# Schema_IOExp_De_Windt_Kyell.net
KiCad netlist of a schematic drawn in EAGLE
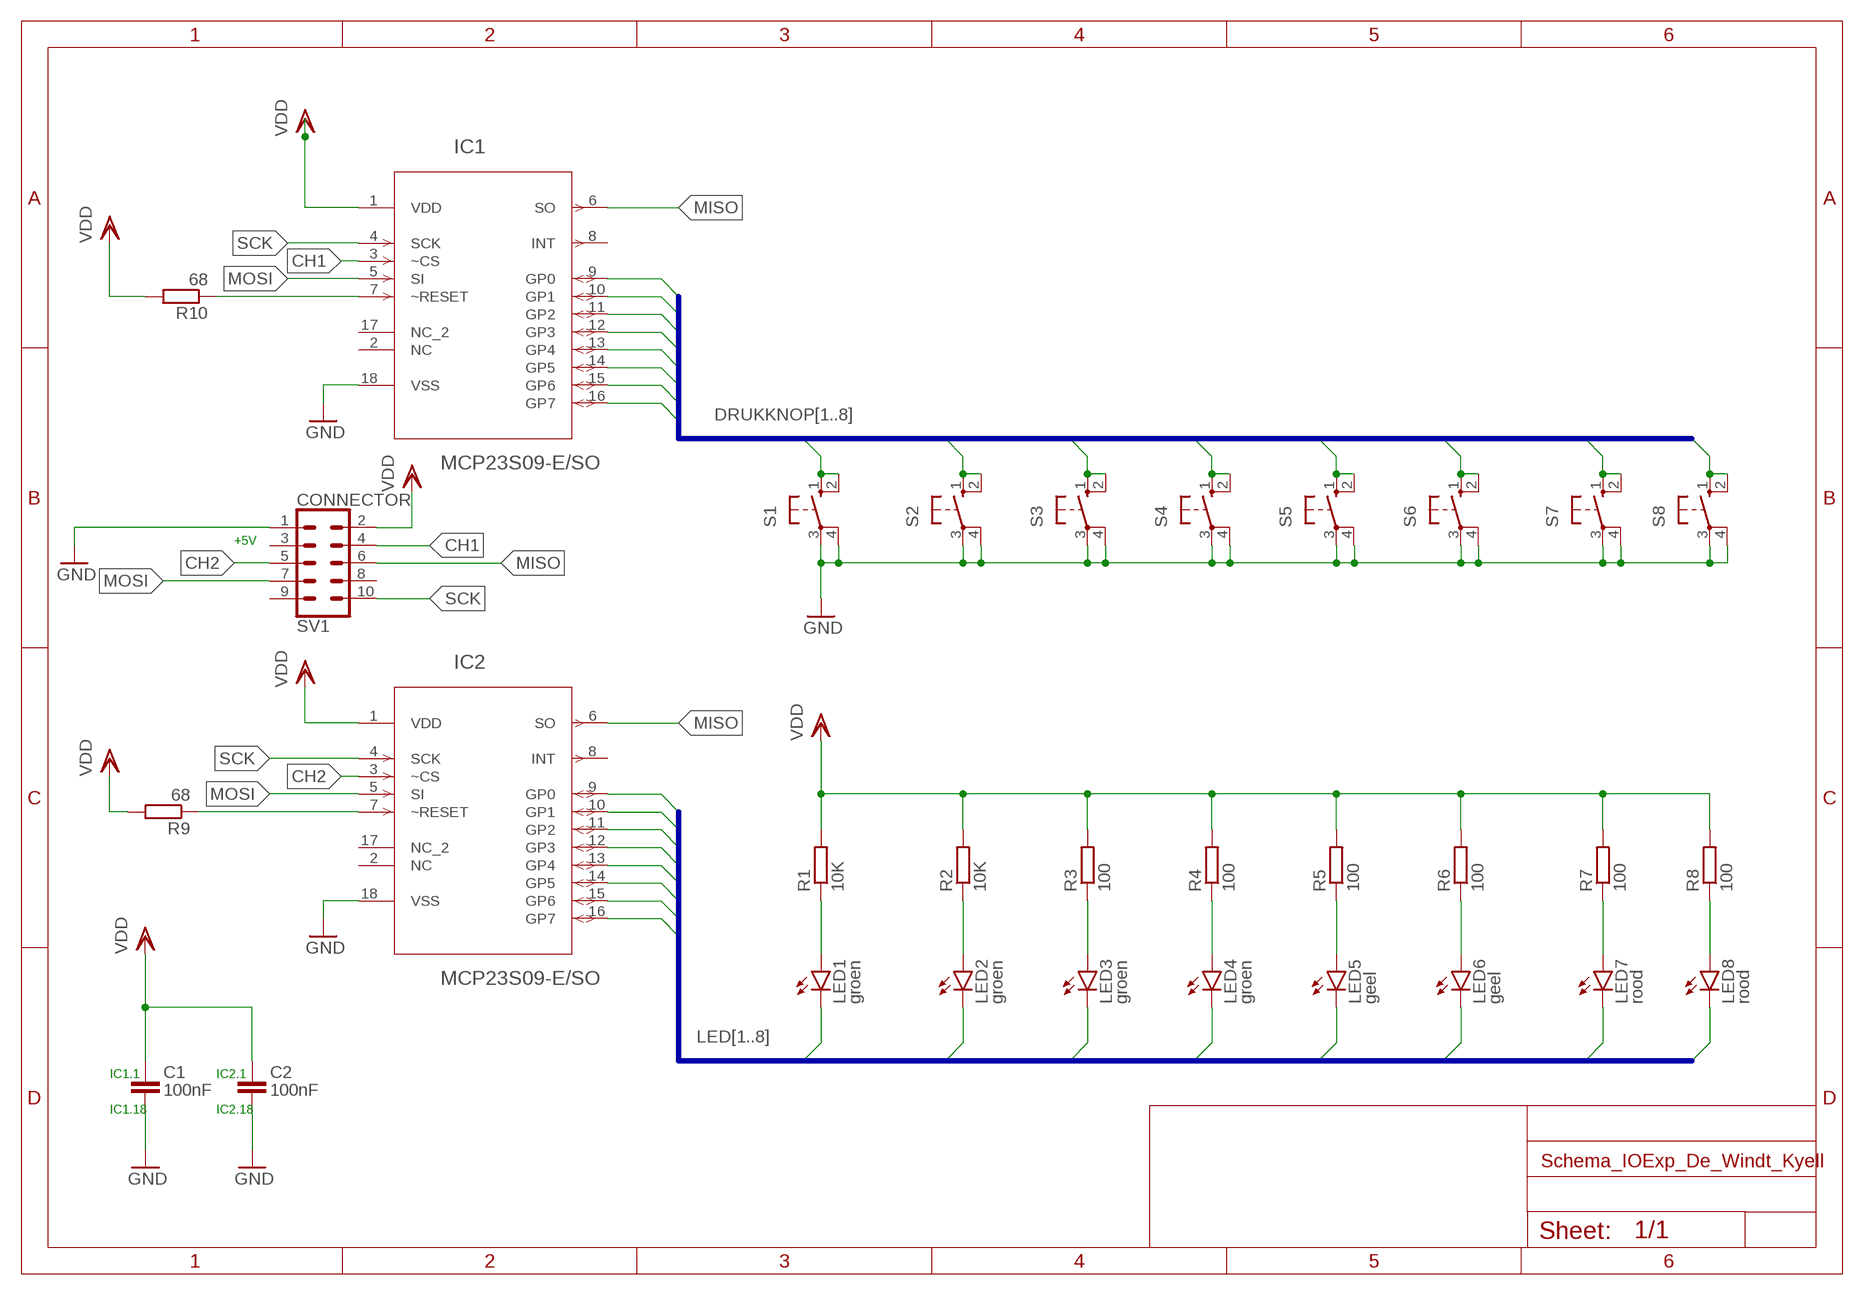
[diagram p0: schematic, sheet 1]

(export (version "E")
  (design (tool "Eeschema 10.0.6"))
  (components
    (comp (ref "C1")
      (value "100nF")
      (footprint "eagle-import:C0805K")
      (libsource (lib "eagle-import") (part "CAPACITORC0805K"))
    )
    (comp (ref "C2")
      (value "100nF")
      (footprint "eagle-import:C0805K")
      (libsource (lib "eagle-import") (part "CAPACITORC0805K"))
    )
    (comp (ref "CONNECTOR")
      (value "SV1")
      (footprint "eagle-import:2X5-SHROUDED")
      (libsource (lib "eagle-import") (part "CONN_05X2SHD"))
    )
    (comp (ref "IC1")
      (value "MCP23S09-E/SO")
      (footprint "eagle-import:SOIC127P1030X265-18N")
      (fields (field (name "MPN") "McP23S09-E/SO"))
      (libsource (lib "eagle-import") (part "MCP23S09-E/SO"))
    )
    (comp (ref "IC2")
      (value "MCP23S09-E/SO")
      (footprint "eagle-import:SOIC127P1030X265-18N")
      (fields (field (name "MPN") "McP23S09-E/SO"))
      (libsource (lib "eagle-import") (part "MCP23S09-E/SO"))
    )
    (comp (ref "LED1")
      (value "groen")
      (footprint "eagle-import:CHIPLED_0805")
      (libsource (lib "eagle-import") (part "LEDCHIPLED_0805"))
    )
    (comp (ref "LED2")
      (value "groen")
      (footprint "eagle-import:CHIPLED_0805")
      (libsource (lib "eagle-import") (part "LEDCHIPLED_0805"))
    )
    (comp (ref "LED3")
      (value "groen")
      (footprint "eagle-import:CHIPLED_0805")
      (libsource (lib "eagle-import") (part "LEDCHIPLED_0805"))
    )
    (comp (ref "LED4")
      (value "groen")
      (footprint "eagle-import:CHIPLED_0805")
      (libsource (lib "eagle-import") (part "LEDCHIPLED_0805"))
    )
    (comp (ref "LED5")
      (value "geel")
      (footprint "eagle-import:CHIPLED_0805")
      (libsource (lib "eagle-import") (part "LEDCHIPLED_0805"))
    )
    (comp (ref "LED6")
      (value "geel")
      (footprint "eagle-import:CHIPLED_0805")
      (libsource (lib "eagle-import") (part "LEDCHIPLED_0805"))
    )
    (comp (ref "LED7")
      (value "rood")
      (footprint "eagle-import:CHIPLED_0805")
      (libsource (lib "eagle-import") (part "LEDCHIPLED_0805"))
    )
    (comp (ref "LED8")
      (value "rood")
      (footprint "eagle-import:CHIPLED_0805")
      (libsource (lib "eagle-import") (part "LEDCHIPLED_0805"))
    )
    (comp (ref "R1")
      (value "10K")
      (footprint "eagle-import:R0805")
      (libsource (lib "eagle-import") (part "R-EU_R0805"))
    )
    (comp (ref "R2")
      (value "10K")
      (footprint "eagle-import:R0805")
      (libsource (lib "eagle-import") (part "R-EU_R0805"))
    )
    (comp (ref "R3")
      (value "100")
      (footprint "eagle-import:R0805")
      (libsource (lib "eagle-import") (part "R-EU_R0805"))
    )
    (comp (ref "R4")
      (value "100")
      (footprint "eagle-import:R0805")
      (libsource (lib "eagle-import") (part "R-EU_R0805"))
    )
    (comp (ref "R5")
      (value "100")
      (footprint "eagle-import:R0805")
      (libsource (lib "eagle-import") (part "R-EU_R0805"))
    )
    (comp (ref "R6")
      (value "100")
      (footprint "eagle-import:R0805")
      (libsource (lib "eagle-import") (part "R-EU_R0805"))
    )
    (comp (ref "R7")
      (value "100")
      (footprint "eagle-import:R0805")
      (libsource (lib "eagle-import") (part "R-EU_R0805"))
    )
    (comp (ref "R8")
      (value "100")
      (footprint "eagle-import:R0805")
      (libsource (lib "eagle-import") (part "R-EU_R0805"))
    )
    (comp (ref "R9")
      (value "68")
      (footprint "eagle-import:R0805")
      (libsource (lib "eagle-import") (part "R-EU_R0805"))
    )
    (comp (ref "R10")
      (value "68")
      (footprint "eagle-import:R0805")
      (libsource (lib "eagle-import") (part "R-EU_R0805"))
    )
    (comp (ref "S1")
      (value "10-XX")
      (footprint "eagle-import:B3F-10XX")
      (fields (field (name "MPN") "B3F-1000"))
      (libsource (lib "eagle-import") (part "10-XX"))
    )
    (comp (ref "S2")
      (value "10-XX")
      (footprint "eagle-import:B3F-10XX")
      (fields (field (name "MPN") "B3F-1000"))
      (libsource (lib "eagle-import") (part "10-XX"))
    )
    (comp (ref "S3")
      (value "10-XX")
      (footprint "eagle-import:B3F-10XX")
      (fields (field (name "MPN") "B3F-1000"))
      (libsource (lib "eagle-import") (part "10-XX"))
    )
    (comp (ref "S4")
      (value "10-XX")
      (footprint "eagle-import:B3F-10XX")
      (fields (field (name "MPN") "B3F-1000"))
      (libsource (lib "eagle-import") (part "10-XX"))
    )
    (comp (ref "S5")
      (value "10-XX")
      (footprint "eagle-import:B3F-10XX")
      (fields (field (name "MPN") "B3F-1000"))
      (libsource (lib "eagle-import") (part "10-XX"))
    )
    (comp (ref "S6")
      (value "10-XX")
      (footprint "eagle-import:B3F-10XX")
      (fields (field (name "MPN") "B3F-1000"))
      (libsource (lib "eagle-import") (part "10-XX"))
    )
    (comp (ref "S7")
      (value "10-XX")
      (footprint "eagle-import:B3F-10XX")
      (fields (field (name "MPN") "B3F-1000"))
      (libsource (lib "eagle-import") (part "10-XX"))
    )
    (comp (ref "S8")
      (value "10-XX")
      (footprint "eagle-import:B3F-10XX")
      (fields (field (name "MPN") "B3F-1000"))
      (libsource (lib "eagle-import") (part "10-XX"))
    )
  )
  (nets
    (net (code "1") (name "/DRUKKNOP1") (class "Default")
      (node (ref "IC1") (pin "9") (pinfunction "GP0_9") (pintype "bidirectional"))
      (node (ref "S1") (pin "1") (pinfunction "S_1") (pintype "passive"))
      (node (ref "S1") (pin "2") (pinfunction "S1_2") (pintype "passive"))
    )
    (net (code "2") (name "/DRUKKNOP2") (class "Default")
      (node (ref "IC1") (pin "10") (pinfunction "GP1_10") (pintype "bidirectional"))
      (node (ref "S2") (pin "1") (pinfunction "S_1") (pintype "passive"))
      (node (ref "S2") (pin "2") (pinfunction "S1_2") (pintype "passive"))
    )
    (net (code "3") (name "/DRUKKNOP3") (class "Default")
      (node (ref "IC1") (pin "11") (pinfunction "GP2_11") (pintype "bidirectional"))
      (node (ref "S3") (pin "1") (pinfunction "S_1") (pintype "passive"))
      (node (ref "S3") (pin "2") (pinfunction "S1_2") (pintype "passive"))
    )
    (net (code "4") (name "/DRUKKNOP4") (class "Default")
      (node (ref "IC1") (pin "12") (pinfunction "GP3_12") (pintype "bidirectional"))
      (node (ref "S4") (pin "1") (pinfunction "S_1") (pintype "passive"))
      (node (ref "S4") (pin "2") (pinfunction "S1_2") (pintype "passive"))
    )
    (net (code "5") (name "/DRUKKNOP5") (class "Default")
      (node (ref "IC1") (pin "13") (pinfunction "GP4_13") (pintype "bidirectional"))
      (node (ref "S5") (pin "1") (pinfunction "S_1") (pintype "passive"))
      (node (ref "S5") (pin "2") (pinfunction "S1_2") (pintype "passive"))
    )
    (net (code "6") (name "/DRUKKNOP6") (class "Default")
      (node (ref "IC1") (pin "14") (pinfunction "GP5_14") (pintype "bidirectional"))
      (node (ref "S6") (pin "1") (pinfunction "S_1") (pintype "passive"))
      (node (ref "S6") (pin "2") (pinfunction "S1_2") (pintype "passive"))
    )
    (net (code "7") (name "/DRUKKNOP7") (class "Default")
      (node (ref "IC1") (pin "15") (pinfunction "GP6_15") (pintype "bidirectional"))
      (node (ref "S7") (pin "1") (pinfunction "S_1") (pintype "passive"))
      (node (ref "S7") (pin "2") (pinfunction "S1_2") (pintype "passive"))
    )
    (net (code "8") (name "/DRUKKNOP8") (class "Default")
      (node (ref "IC1") (pin "16") (pinfunction "GP7_16") (pintype "bidirectional"))
      (node (ref "S8") (pin "1") (pinfunction "S_1") (pintype "passive"))
      (node (ref "S8") (pin "2") (pinfunction "S1_2") (pintype "passive"))
    )
    (net (code "10") (name "/LED1") (class "Default")
      (node (ref "IC2") (pin "9") (pinfunction "GP0_9") (pintype "bidirectional"))
      (node (ref "LED1") (pin "C") (pinfunction "C_C") (pintype "passive"))
    )
    (net (code "11") (name "/LED2") (class "Default")
      (node (ref "IC2") (pin "10") (pinfunction "GP1_10") (pintype "bidirectional"))
      (node (ref "LED2") (pin "C") (pinfunction "C_C") (pintype "passive"))
    )
    (net (code "12") (name "/LED3") (class "Default")
      (node (ref "IC2") (pin "11") (pinfunction "GP2_11") (pintype "bidirectional"))
      (node (ref "LED3") (pin "C") (pinfunction "C_C") (pintype "passive"))
    )
    (net (code "13") (name "/LED4") (class "Default")
      (node (ref "IC2") (pin "12") (pinfunction "GP3_12") (pintype "bidirectional"))
      (node (ref "LED4") (pin "C") (pinfunction "C_C") (pintype "passive"))
    )
    (net (code "14") (name "/LED5") (class "Default")
      (node (ref "IC2") (pin "13") (pinfunction "GP4_13") (pintype "bidirectional"))
      (node (ref "LED5") (pin "C") (pinfunction "C_C") (pintype "passive"))
    )
    (net (code "15") (name "/LED6") (class "Default")
      (node (ref "IC2") (pin "14") (pinfunction "GP5_14") (pintype "bidirectional"))
      (node (ref "LED6") (pin "C") (pinfunction "C_C") (pintype "passive"))
    )
    (net (code "16") (name "/LED7") (class "Default")
      (node (ref "IC2") (pin "15") (pinfunction "GP6_15") (pintype "bidirectional"))
      (node (ref "LED7") (pin "C") (pinfunction "C_C") (pintype "passive"))
    )
    (net (code "17") (name "/LED8") (class "Default")
      (node (ref "IC2") (pin "16") (pinfunction "GP7_16") (pintype "bidirectional"))
      (node (ref "LED8") (pin "C") (pinfunction "C_C") (pintype "passive"))
    )
    (net (code "19") (name "CH1") (class "Default")
      (node (ref "CONNECTOR") (pin "4") (pinfunction "4_4") (pintype "passive"))
      (node (ref "IC1") (pin "3") (pinfunction "~{CS}_3") (pintype "input"))
    )
    (net (code "20") (name "CH2") (class "Default")
      (node (ref "CONNECTOR") (pin "5") (pinfunction "5_5") (pintype "passive"))
      (node (ref "IC2") (pin "3") (pinfunction "~{CS}_3") (pintype "input"))
    )
    (net (code "21") (name "GND") (class "Default")
      (node (ref "C1") (pin "2") (pinfunction "2_2") (pintype "passive"))
      (node (ref "C2") (pin "2") (pinfunction "2_2") (pintype "passive"))
      (node (ref "CONNECTOR") (pin "1") (pinfunction "1_1") (pintype "passive"))
      (node (ref "IC1") (pin "18") (pinfunction "VSS_18") (pintype "power_in"))
      (node (ref "IC2") (pin "18") (pinfunction "VSS_18") (pintype "power_in"))
      (node (ref "S1") (pin "3") (pinfunction "P_3") (pintype "passive"))
      (node (ref "S1") (pin "4") (pinfunction "P1_4") (pintype "passive"))
      (node (ref "S2") (pin "3") (pinfunction "P_3") (pintype "passive"))
      (node (ref "S2") (pin "4") (pinfunction "P1_4") (pintype "passive"))
      (node (ref "S3") (pin "3") (pinfunction "P_3") (pintype "passive"))
      (node (ref "S3") (pin "4") (pinfunction "P1_4") (pintype "passive"))
      (node (ref "S4") (pin "3") (pinfunction "P_3") (pintype "passive"))
      (node (ref "S4") (pin "4") (pinfunction "P1_4") (pintype "passive"))
      (node (ref "S5") (pin "3") (pinfunction "P_3") (pintype "passive"))
      (node (ref "S5") (pin "4") (pinfunction "P1_4") (pintype "passive"))
      (node (ref "S6") (pin "3") (pinfunction "P_3") (pintype "passive"))
      (node (ref "S6") (pin "4") (pinfunction "P1_4") (pintype "passive"))
      (node (ref "S7") (pin "3") (pinfunction "P_3") (pintype "passive"))
      (node (ref "S7") (pin "4") (pinfunction "P1_4") (pintype "passive"))
      (node (ref "S8") (pin "3") (pinfunction "P_3") (pintype "passive"))
      (node (ref "S8") (pin "4") (pinfunction "P1_4") (pintype "passive"))
    )
    (net (code "22") (name "MISO") (class "Default")
      (node (ref "CONNECTOR") (pin "6") (pinfunction "6_6") (pintype "passive"))
      (node (ref "IC1") (pin "6") (pinfunction "SO_6") (pintype "output"))
      (node (ref "IC2") (pin "6") (pinfunction "SO_6") (pintype "output"))
    )
    (net (code "23") (name "MOSI") (class "Default")
      (node (ref "CONNECTOR") (pin "7") (pinfunction "7_7") (pintype "passive"))
      (node (ref "IC1") (pin "5") (pinfunction "SI_5") (pintype "input"))
      (node (ref "IC2") (pin "5") (pinfunction "SI_5") (pintype "input"))
    )
    (net (code "24") (name "Net-(IC1-~{RESET})") (class "Default")
      (node (ref "IC1") (pin "7") (pinfunction "~{RESET}_7") (pintype "input"))
      (node (ref "R10") (pin "1") (pinfunction "1_1") (pintype "passive"))
    )
    (net (code "25") (name "Net-(IC2-~{RESET})") (class "Default")
      (node (ref "IC2") (pin "7") (pinfunction "~{RESET}_7") (pintype "input"))
      (node (ref "R9") (pin "1") (pinfunction "1_1") (pintype "passive"))
    )
    (net (code "26") (name "Net-(LED1-PadA)") (class "Default")
      (node (ref "LED1") (pin "A") (pinfunction "A_A") (pintype "passive"))
      (node (ref "R1") (pin "1") (pinfunction "1_1") (pintype "passive"))
    )
    (net (code "27") (name "Net-(LED2-PadA)") (class "Default")
      (node (ref "LED2") (pin "A") (pinfunction "A_A") (pintype "passive"))
      (node (ref "R2") (pin "1") (pinfunction "1_1") (pintype "passive"))
    )
    (net (code "28") (name "Net-(LED3-PadA)") (class "Default")
      (node (ref "LED3") (pin "A") (pinfunction "A_A") (pintype "passive"))
      (node (ref "R3") (pin "1") (pinfunction "1_1") (pintype "passive"))
    )
    (net (code "29") (name "Net-(LED4-PadA)") (class "Default")
      (node (ref "LED4") (pin "A") (pinfunction "A_A") (pintype "passive"))
      (node (ref "R4") (pin "1") (pinfunction "1_1") (pintype "passive"))
    )
    (net (code "30") (name "Net-(LED5-PadA)") (class "Default")
      (node (ref "LED5") (pin "A") (pinfunction "A_A") (pintype "passive"))
      (node (ref "R5") (pin "1") (pinfunction "1_1") (pintype "passive"))
    )
    (net (code "31") (name "Net-(LED6-PadA)") (class "Default")
      (node (ref "LED6") (pin "A") (pinfunction "A_A") (pintype "passive"))
      (node (ref "R6") (pin "1") (pinfunction "1_1") (pintype "passive"))
    )
    (net (code "32") (name "Net-(LED7-PadA)") (class "Default")
      (node (ref "LED7") (pin "A") (pinfunction "A_A") (pintype "passive"))
      (node (ref "R7") (pin "1") (pinfunction "1_1") (pintype "passive"))
    )
    (net (code "33") (name "Net-(LED8-PadA)") (class "Default")
      (node (ref "LED8") (pin "A") (pinfunction "A_A") (pintype "passive"))
      (node (ref "R8") (pin "1") (pinfunction "1_1") (pintype "passive"))
    )
    (net (code "34") (name "SCK") (class "Default")
      (node (ref "CONNECTOR") (pin "10") (pinfunction "10_10") (pintype "passive"))
      (node (ref "IC1") (pin "4") (pinfunction "SCK_4") (pintype "input"))
      (node (ref "IC2") (pin "4") (pinfunction "SCK_4") (pintype "input"))
    )
    (net (code "35") (name "VDD") (class "Default")
      (node (ref "C1") (pin "1") (pinfunction "1_1") (pintype "passive"))
      (node (ref "C2") (pin "1") (pinfunction "1_1") (pintype "passive"))
      (node (ref "CONNECTOR") (pin "2") (pinfunction "2_2") (pintype "passive"))
      (node (ref "IC1") (pin "1") (pinfunction "VDD_1") (pintype "power_in"))
      (node (ref "IC2") (pin "1") (pinfunction "VDD_1") (pintype "power_in"))
      (node (ref "R1") (pin "2") (pinfunction "2_2") (pintype "passive"))
      (node (ref "R10") (pin "2") (pinfunction "2_2") (pintype "passive"))
      (node (ref "R2") (pin "2") (pinfunction "2_2") (pintype "passive"))
      (node (ref "R3") (pin "2") (pinfunction "2_2") (pintype "passive"))
      (node (ref "R4") (pin "2") (pinfunction "2_2") (pintype "passive"))
      (node (ref "R5") (pin "2") (pinfunction "2_2") (pintype "passive"))
      (node (ref "R6") (pin "2") (pinfunction "2_2") (pintype "passive"))
      (node (ref "R7") (pin "2") (pinfunction "2_2") (pintype "passive"))
      (node (ref "R8") (pin "2") (pinfunction "2_2") (pintype "passive"))
      (node (ref "R9") (pin "2") (pinfunction "2_2") (pintype "passive"))
    )
    (net (code "36") (name "unconnected-(CONNECTOR-Pad3)") (class "Default")
      (node (ref "CONNECTOR") (pin "3") (pinfunction "3_3") (pintype "passive"))
    )
    (net (code "37") (name "unconnected-(CONNECTOR-Pad8)") (class "Default")
      (node (ref "CONNECTOR") (pin "8") (pinfunction "8_8") (pintype "passive"))
    )
    (net (code "38") (name "unconnected-(CONNECTOR-Pad9)") (class "Default")
      (node (ref "CONNECTOR") (pin "9") (pinfunction "9_9") (pintype "passive"))
    )
    (net (code "39") (name "unconnected-(IC1-INT-Pad8)") (class "Default")
      (node (ref "IC1") (pin "8") (pinfunction "INT_8") (pintype "output"))
    )
    (net (code "40") (name "unconnected-(IC1-NC-Pad2)") (class "Default")
      (node (ref "IC1") (pin "2") (pinfunction "NC_2") (pintype "no_connect"))
    )
    (net (code "41") (name "unconnected-(IC1-NC_2-Pad17)") (class "Default")
      (node (ref "IC1") (pin "17") (pinfunction "NC_2_17") (pintype "no_connect"))
    )
    (net (code "42") (name "unconnected-(IC2-INT-Pad8)") (class "Default")
      (node (ref "IC2") (pin "8") (pinfunction "INT_8") (pintype "output"))
    )
    (net (code "43") (name "unconnected-(IC2-NC-Pad2)") (class "Default")
      (node (ref "IC2") (pin "2") (pinfunction "NC_2") (pintype "no_connect"))
    )
    (net (code "44") (name "unconnected-(IC2-NC_2-Pad17)") (class "Default")
      (node (ref "IC2") (pin "17") (pinfunction "NC_2_17") (pintype "no_connect"))
    )
  )
)
